# Fuente.net
KiCad netlist of a schematic drawn in EAGLE
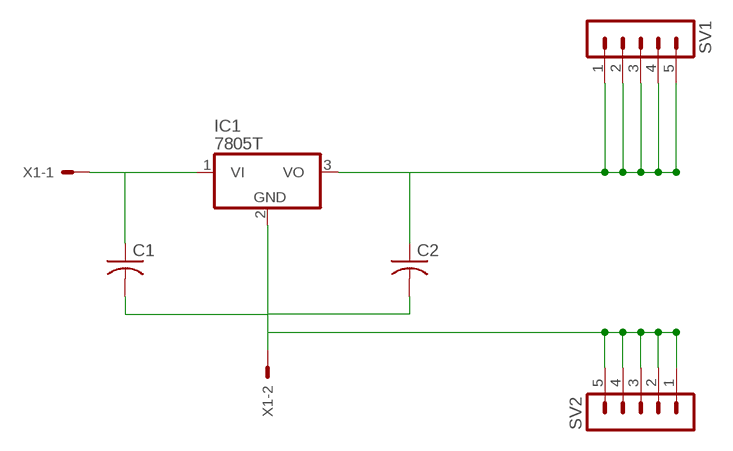
[diagram p0: schematic, sheet 1]

(export (version "E")
  (design (tool "Eeschema 10.0.6"))
  (components
    (comp (ref "C1")
      (value "C-US025-030X050")
      (footprint "eagle-import:C025-030X050")
      (libsource (lib "eagle-import") (part "C-US025-030X050"))
    )
    (comp (ref "C2")
      (value "C-US025-030X050")
      (footprint "eagle-import:C025-030X050")
      (libsource (lib "eagle-import") (part "C-US025-030X050"))
    )
    (comp (ref "IC1")
      (value "7805T")
      (footprint "eagle-import:TO220H")
      (libsource (lib "eagle-import") (part "78T05"))
    )
    (comp (ref "SV1")
      (value "MA05-1")
      (footprint "eagle-import:MA05-1")
      (libsource (lib "eagle-import") (part "MA05-1"))
    )
    (comp (ref "SV2")
      (value "MA05-1")
      (footprint "eagle-import:MA05-1")
      (libsource (lib "eagle-import") (part "MA05-1"))
    )
    (comp (ref "X1")
      (value "KK-156-2")
      (footprint "eagle-import:KK-156-2")
      (libsource (lib "eagle-import") (part "KK-156-2"))
    )
  )
  (nets
    (net (code "1") (name "Net-(IC1-GND)") (class "Default")
      (node (ref "C1") (pin "2") (pinfunction "2_2") (pintype "passive"))
      (node (ref "C2") (pin "2") (pinfunction "2_2") (pintype "passive"))
      (node (ref "IC1") (pin "2") (pinfunction "GND_2") (pintype "passive"))
      (node (ref "SV2") (pin "1") (pinfunction "1_1") (pintype "passive"))
      (node (ref "SV2") (pin "2") (pinfunction "2_2") (pintype "passive"))
      (node (ref "SV2") (pin "3") (pinfunction "3_3") (pintype "passive"))
      (node (ref "SV2") (pin "4") (pinfunction "4_4") (pintype "passive"))
      (node (ref "SV2") (pin "5") (pinfunction "5_5") (pintype "passive"))
      (node (ref "X1") (pin "2") (pinfunction "S_2") (pintype "passive"))
    )
    (net (code "2") (name "Net-(IC1-VI)") (class "Default")
      (node (ref "C1") (pin "1") (pinfunction "1_1") (pintype "passive"))
      (node (ref "IC1") (pin "1") (pinfunction "VI_1") (pintype "input"))
      (node (ref "X1") (pin "1") (pinfunction "S_1") (pintype "passive"))
    )
    (net (code "3") (name "Net-(IC1-VO)") (class "Default")
      (node (ref "C2") (pin "1") (pinfunction "1_1") (pintype "passive"))
      (node (ref "IC1") (pin "3") (pinfunction "VO_3") (pintype "passive"))
      (node (ref "SV1") (pin "1") (pinfunction "1_1") (pintype "passive"))
      (node (ref "SV1") (pin "2") (pinfunction "2_2") (pintype "passive"))
      (node (ref "SV1") (pin "3") (pinfunction "3_3") (pintype "passive"))
      (node (ref "SV1") (pin "4") (pinfunction "4_4") (pintype "passive"))
      (node (ref "SV1") (pin "5") (pinfunction "5_5") (pintype "passive"))
    )
  )
)
